# V0p2_Main_PCB2.net
KiCad netlist of a schematic drawn in EAGLE
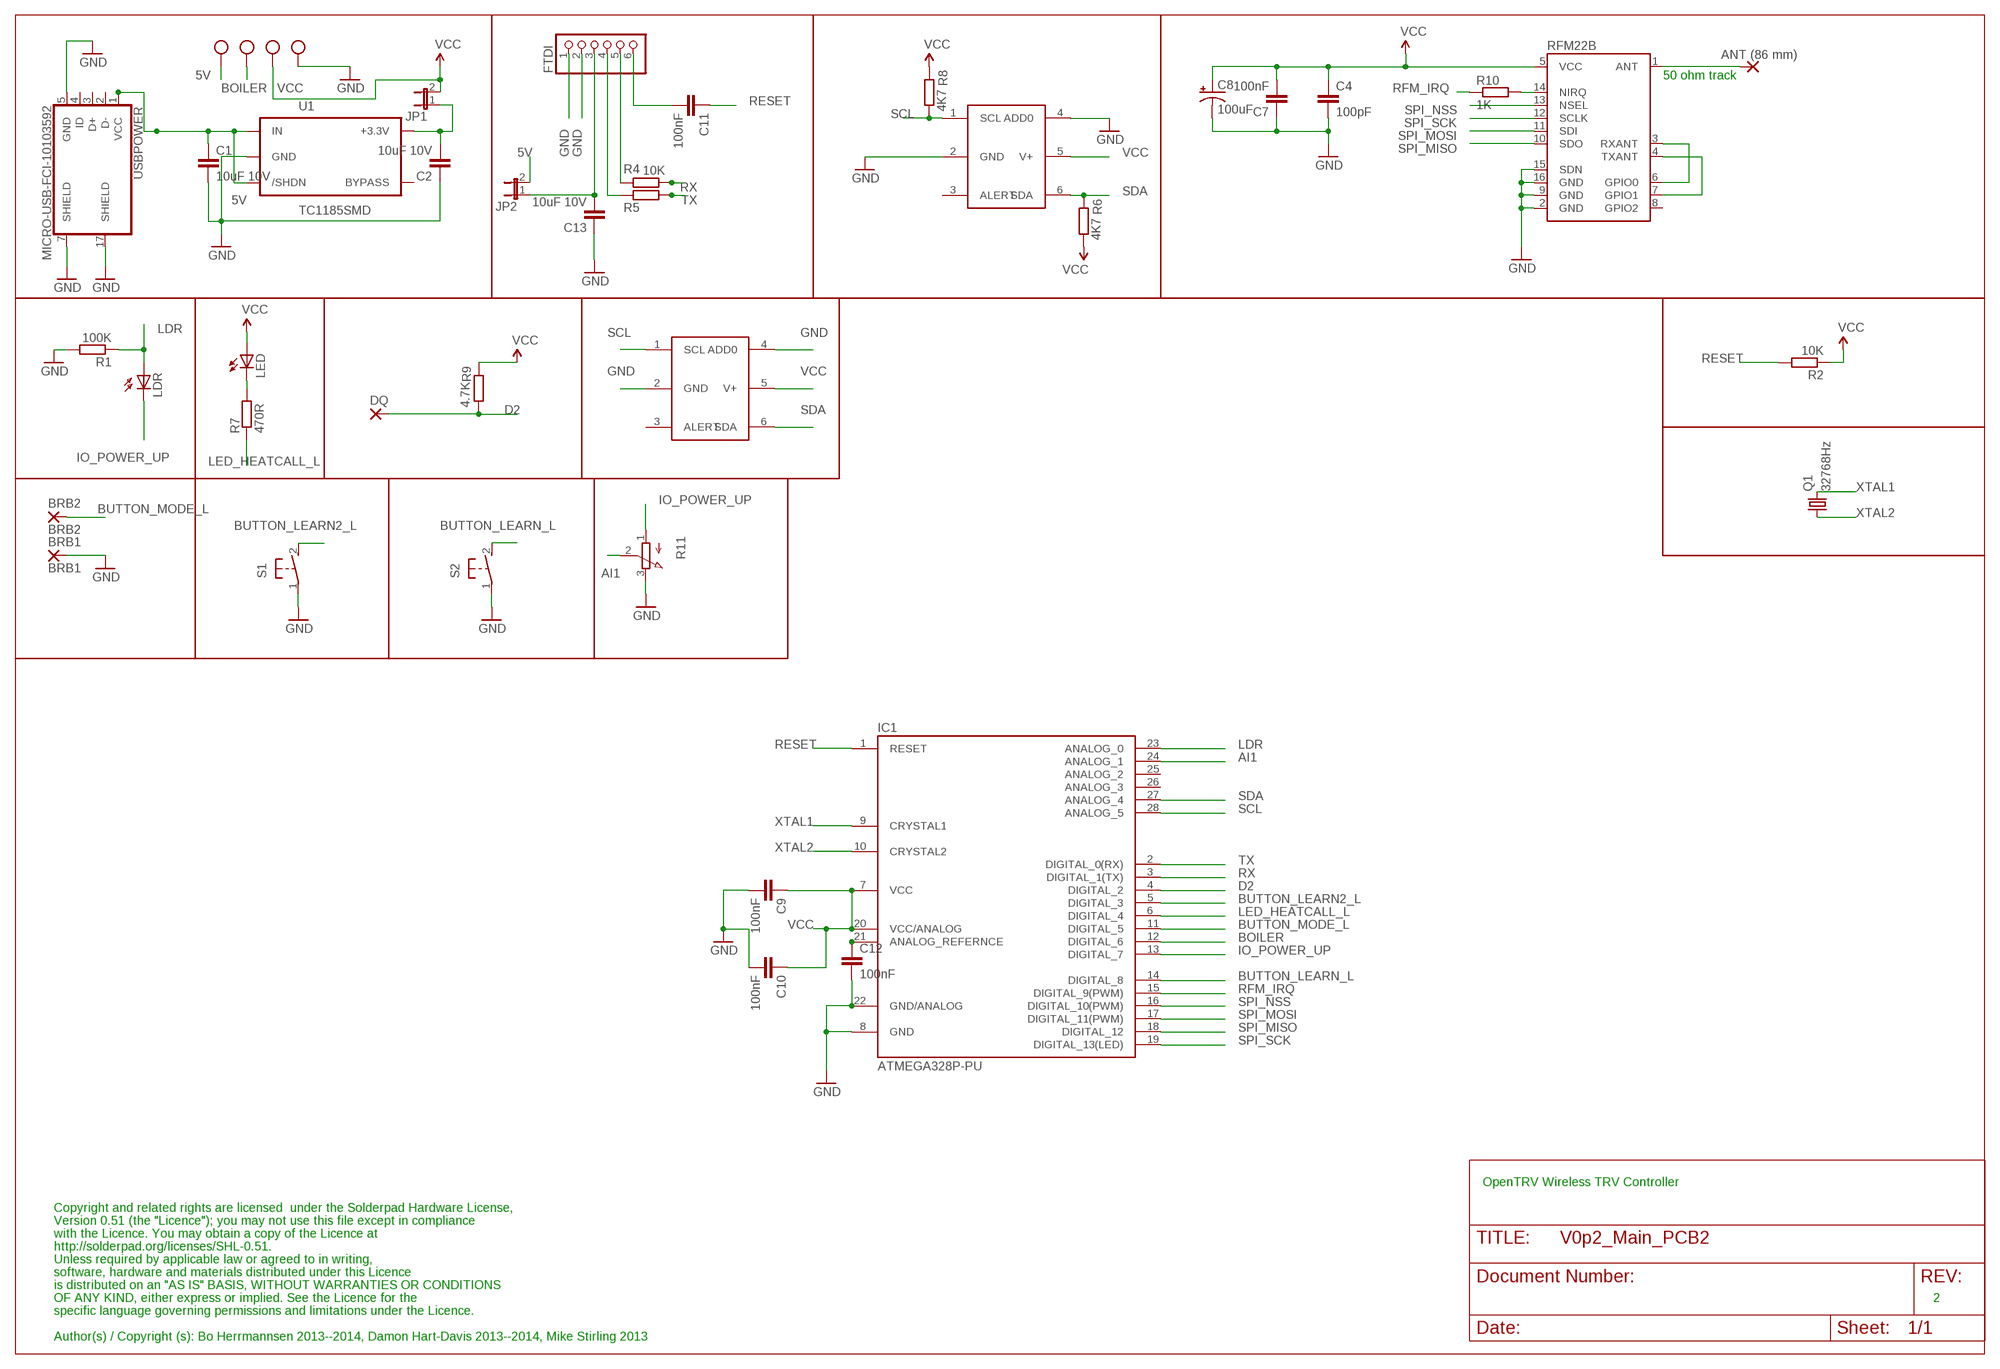
[diagram p0: schematic, sheet 1]

(export (version "E")
  (design (tool "Eeschema 10.0.6"))
  (components
    (comp (ref "ANT")
      (value "ANT (86 mm)")
      (footprint "eagle-import:2,15_1,0")
      (libsource (lib "eagle-import") (part "2,15/1,0"))
    )
    (comp (ref "BRB1")
      (value "BRB1")
      (footprint "eagle-import:2,15_1,0")
      (libsource (lib "eagle-import") (part "2,15/1,0"))
    )
    (comp (ref "BRB2")
      (value "BRB2")
      (footprint "eagle-import:2,15_1,0")
      (libsource (lib "eagle-import") (part "2,15/1,0"))
    )
    (comp (ref "C1")
      (value "10uF 10V")
      (footprint "eagle-import:0603-CAP")
      (libsource (lib "eagle-import") (part "CAP0603-CAP"))
    )
    (comp (ref "C2")
      (value "10uF 10V")
      (footprint "eagle-import:0603-CAP")
      (libsource (lib "eagle-import") (part "CAP0603-CAP"))
    )
    (comp (ref "C4")
      (value "100pF")
      (footprint "eagle-import:0603-CAP")
      (libsource (lib "eagle-import") (part "CAP0603-CAP"))
    )
    (comp (ref "C7")
      (value "100nF")
      (footprint "eagle-import:0603-CAP")
      (libsource (lib "eagle-import") (part "CAP0603-CAP"))
    )
    (comp (ref "C8")
      (value "100uF")
      (footprint "eagle-import:EIA3216")
      (libsource (lib "eagle-import") (part "CAP_POL1206"))
    )
    (comp (ref "C9")
      (value "100nF")
      (footprint "eagle-import:0603-CAP")
      (libsource (lib "eagle-import") (part "CAP0603-CAP"))
    )
    (comp (ref "C10")
      (value "100nF")
      (footprint "eagle-import:0603-CAP")
      (libsource (lib "eagle-import") (part "CAP0603-CAP"))
    )
    (comp (ref "C11")
      (value "100nF")
      (footprint "eagle-import:0603-CAP")
      (libsource (lib "eagle-import") (part "CAP0603-CAP"))
    )
    (comp (ref "C12")
      (value "100nF")
      (footprint "eagle-import:0603-CAP")
      (libsource (lib "eagle-import") (part "CAP0603-CAP"))
    )
    (comp (ref "C13")
      (value "10uF 10V")
      (footprint "eagle-import:0603-CAP")
      (libsource (lib "eagle-import") (part "CAP0603-CAP"))
    )
    (comp (ref "DQ")
      (value "2,15/1,0")
      (footprint "eagle-import:2,15_1,0")
      (libsource (lib "eagle-import") (part "2,15/1,0"))
    )
    (comp (ref "FTDI")
      (value "PINHD-1X6/90")
      (footprint "eagle-import:1X06_90")
      (libsource (lib "eagle-import") (part "PINHD-1X6/90"))
    )
    (comp (ref "IC1")
      (value "ATMEGA328P-PU")
      (footprint "eagle-import:DIL28-3")
      (libsource (lib "eagle-import") (part "ATMEGA8-PU"))
    )
    (comp (ref "JP1")
      (value "JP1E")
      (footprint "eagle-import:JP1")
      (libsource (lib "eagle-import") (part "JP1E"))
    )
    (comp (ref "JP2")
      (value "JP1E")
      (footprint "eagle-import:JP1")
      (libsource (lib "eagle-import") (part "JP1E"))
    )
    (comp (ref "LDR")
      (value "BPX65")
      (footprint "eagle-import:BPX65")
      (fields (field (name "MPN") "BPX65."))
      (libsource (lib "eagle-import") (part "BPX65"))
    )
    (comp (ref "LED")
      (value "LED3MM")
      (footprint "eagle-import:LED3MM")
      (libsource (lib "eagle-import") (part "LED3MM"))
    )
    (comp (ref "Q1")
      (value "32768Hz")
      (footprint "eagle-import:MC-306")
      (fields (field (name "MPN") "MC-306 60.0KHZ  100PPM ,12.5PF"))
      (libsource (lib "eagle-import") (part "MC-306"))
    )
    (comp (ref "R1")
      (value "100K")
      (footprint "eagle-import:R0603")
      (libsource (lib "eagle-import") (part "R-EU_R0603"))
    )
    (comp (ref "R2")
      (value "10K")
      (footprint "eagle-import:R0603")
      (libsource (lib "eagle-import") (part "R-EU_R0603"))
    )
    (comp (ref "R4")
      (value "10K")
      (footprint "eagle-import:R0603")
      (libsource (lib "eagle-import") (part "R-EU_R0603"))
    )
    (comp (ref "R5")
      (value "10K")
      (footprint "eagle-import:R0603")
      (libsource (lib "eagle-import") (part "R-EU_R0603"))
    )
    (comp (ref "R6")
      (value "4K7")
      (footprint "eagle-import:R0603")
      (libsource (lib "eagle-import") (part "R-EU_R0603"))
    )
    (comp (ref "R7")
      (value "470R")
      (footprint "eagle-import:R0603")
      (libsource (lib "eagle-import") (part "R-EU_R0603"))
    )
    (comp (ref "R8")
      (value "4K7")
      (footprint "eagle-import:R0603")
      (libsource (lib "eagle-import") (part "R-EU_R0603"))
    )
    (comp (ref "R9")
      (value "4.7K")
      (footprint "eagle-import:R0603")
      (libsource (lib "eagle-import") (part "R-EU_R0603"))
    )
    (comp (ref "R10")
      (value "1K")
      (footprint "eagle-import:R0603")
      (libsource (lib "eagle-import") (part "R-EU_R0603"))
    )
    (comp (ref "R11")
      (value "EVUE2A")
      (footprint "eagle-import:EVUE")
      (libsource (lib "eagle-import") (part "EVUE2A"))
    )
    (comp (ref "RFM22B")
      (value "RFM22SMD")
      (footprint "eagle-import:RFM22-XXX-S2")
      (libsource (lib "eagle-import") (part "RFM22SMD"))
    )
    (comp (ref "S1")
      (value "31-XX")
      (footprint "eagle-import:B3F-31XX")
      (libsource (lib "eagle-import") (part "31-XX"))
    )
    (comp (ref "S2")
      (value "31-XX")
      (footprint "eagle-import:B3F-31XX")
      (libsource (lib "eagle-import") (part "31-XX"))
    )
    (comp (ref "TMP1")
      (value "TMP1")
      (footprint "eagle-import:TMP112")
      (libsource (lib "eagle-import") (part "TMP112"))
    )
    (comp (ref "TMP2")
      (value "TMP2")
      (footprint "eagle-import:TMP112")
      (libsource (lib "eagle-import") (part "TMP112_2_TMP112"))
    )
    (comp (ref "U1")
      (value "TC1185SMD")
      (footprint "eagle-import:TC1185")
      (libsource (lib "eagle-import") (part "TC1185SMD"))
    )
    (comp (ref "USBPOWER")
      (value "MICRO-USB-FCI-10103592")
      (footprint "eagle-import:MICRO-USB-FCI-10103592")
      (libsource (lib "eagle-import") (part "MICRO-USB-FCI-10103592"))
    )
    (comp (ref "X1")
      (value "W237-102")
      (footprint "eagle-import:SCREWTERMINAL")
      (fields (field (name "MPN") "237-102"))
      (libsource (lib "eagle-import") (part "W237-102"))
    )
    (comp (ref "X2")
      (value "W237-102")
      (footprint "eagle-import:SCREWTERMINAL")
      (fields (field (name "MPN") "237-102"))
      (libsource (lib "eagle-import") (part "W237-102"))
    )
  )
  (nets
    (net (code "1") (name "/5V") (class "Default")
      (node (ref "C1") (pin "1") (pinfunction "1_1") (pintype "passive"))
      (node (ref "JP2") (pin "2") (pinfunction "2_2") (pintype "passive"))
      (node (ref "U1") (pin "1") (pinfunction "IN_1") (pintype "passive"))
      (node (ref "U1") (pin "3") (pinfunction "/SHDN_3") (pintype "passive"))
      (node (ref "USBPOWER") (pin "1") (pinfunction "VCC_1") (pintype "bidirectional"))
      (node (ref "X1") (pin "2") (pinfunction "KL_2") (pintype "passive"))
    )
    (net (code "2") (name "/AI1") (class "Default")
      (node (ref "IC1") (pin "24") (pinfunction "ANALOG_1_24") (pintype "bidirectional"))
      (node (ref "R11") (pin "2") (pinfunction "S_2") (pintype "passive"))
    )
    (net (code "3") (name "/BOILER") (class "Default")
      (node (ref "IC1") (pin "12") (pinfunction "DIGITAL_6_12") (pintype "bidirectional"))
      (node (ref "X1") (pin "1") (pinfunction "KL_1") (pintype "passive"))
    )
    (net (code "4") (name "/BUTTON_LEARN2_L") (class "Default")
      (node (ref "IC1") (pin "5") (pinfunction "DIGITAL_3_5") (pintype "bidirectional"))
      (node (ref "S1") (pin "2") (pinfunction "S_2") (pintype "passive"))
    )
    (net (code "5") (name "/BUTTON_LEARN_L") (class "Default")
      (node (ref "IC1") (pin "14") (pinfunction "DIGITAL_8_14") (pintype "bidirectional"))
      (node (ref "S2") (pin "2") (pinfunction "S_2") (pintype "passive"))
    )
    (net (code "6") (name "/BUTTON_MODE_L") (class "Default")
      (node (ref "BRB2") (pin "1") (pinfunction "P_1") (pintype "passive"))
      (node (ref "IC1") (pin "11") (pinfunction "DIGITAL_5_11") (pintype "bidirectional"))
    )
    (net (code "7") (name "/D2") (class "Default")
      (node (ref "DQ") (pin "1") (pinfunction "P_1") (pintype "passive"))
      (node (ref "IC1") (pin "4") (pinfunction "DIGITAL_2_4") (pintype "bidirectional"))
      (node (ref "R9") (pin "1") (pinfunction "1_1") (pintype "passive"))
    )
    (net (code "8") (name "/IO_POWER_UP") (class "Default")
      (node (ref "IC1") (pin "13") (pinfunction "DIGITAL_7_13") (pintype "bidirectional"))
      (node (ref "LDR") (pin "K") (pinfunction "C_K") (pintype "passive"))
      (node (ref "R11") (pin "1") (pinfunction "A_1") (pintype "passive"))
    )
    (net (code "9") (name "/LDR") (class "Default")
      (node (ref "IC1") (pin "23") (pinfunction "ANALOG_0_23") (pintype "bidirectional"))
      (node (ref "LDR") (pin "A") (pinfunction "A_A") (pintype "passive"))
      (node (ref "R1") (pin "1") (pinfunction "1_1") (pintype "passive"))
    )
    (net (code "10") (name "/LED_HEATCALL_L") (class "Default")
      (node (ref "IC1") (pin "6") (pinfunction "DIGITAL_4_6") (pintype "bidirectional"))
      (node (ref "R7") (pin "1") (pinfunction "1_1") (pintype "passive"))
    )
    (net (code "11") (name "/RESET") (class "Default")
      (node (ref "C11") (pin "1") (pinfunction "1_1") (pintype "passive"))
      (node (ref "IC1") (pin "1") (pinfunction "RESET_1") (pintype "bidirectional"))
      (node (ref "R2") (pin "2") (pinfunction "2_2") (pintype "passive"))
    )
    (net (code "12") (name "/RFM_IRQ") (class "Default")
      (node (ref "IC1") (pin "15") (pinfunction "DIGITAL_9(PWM)_15") (pintype "bidirectional"))
      (node (ref "R10") (pin "1") (pinfunction "1_1") (pintype "passive"))
    )
    (net (code "13") (name "/RX") (class "Default")
      (node (ref "IC1") (pin "3") (pinfunction "DIGITAL_1(TX)_3") (pintype "bidirectional"))
      (node (ref "R4") (pin "1") (pinfunction "1_1") (pintype "passive"))
    )
    (net (code "14") (name "/SCL") (class "Default")
      (node (ref "IC1") (pin "28") (pinfunction "ANALOG_5_28") (pintype "bidirectional"))
      (node (ref "R8") (pin "1") (pinfunction "1_1") (pintype "passive"))
      (node (ref "TMP1") (pin "1") (pinfunction "SCL_1") (pintype "bidirectional"))
      (node (ref "TMP2") (pin "1") (pinfunction "SCL_1") (pintype "bidirectional"))
    )
    (net (code "15") (name "/SDA") (class "Default")
      (node (ref "IC1") (pin "27") (pinfunction "ANALOG_4_27") (pintype "bidirectional"))
      (node (ref "R6") (pin "2") (pinfunction "2_2") (pintype "passive"))
      (node (ref "TMP1") (pin "6") (pinfunction "SDA_6") (pintype "bidirectional"))
      (node (ref "TMP2") (pin "6") (pinfunction "SDA_6") (pintype "bidirectional"))
    )
    (net (code "16") (name "/SPI_MISO") (class "Default")
      (node (ref "IC1") (pin "18") (pinfunction "DIGITAL_12_18") (pintype "bidirectional"))
      (node (ref "RFM22B") (pin "10") (pinfunction "SDO_10") (pintype "output"))
    )
    (net (code "17") (name "/SPI_MOSI") (class "Default")
      (node (ref "IC1") (pin "17") (pinfunction "DIGITAL_11(PWM)_17") (pintype "bidirectional"))
      (node (ref "RFM22B") (pin "11") (pinfunction "SDI_11") (pintype "input"))
    )
    (net (code "18") (name "/SPI_NSS") (class "Default")
      (node (ref "IC1") (pin "16") (pinfunction "DIGITAL_10(PWM)_16") (pintype "bidirectional"))
      (node (ref "RFM22B") (pin "13") (pinfunction "NSEL_13") (pintype "input"))
    )
    (net (code "19") (name "/SPI_SCK") (class "Default")
      (node (ref "IC1") (pin "19") (pinfunction "DIGITAL_13(LED)_19") (pintype "bidirectional"))
      (node (ref "RFM22B") (pin "12") (pinfunction "SCLK_12") (pintype "input"))
    )
    (net (code "20") (name "/TX") (class "Default")
      (node (ref "IC1") (pin "2") (pinfunction "DIGITAL_0(RX)_2") (pintype "bidirectional"))
      (node (ref "R5") (pin "1") (pinfunction "1_1") (pintype "passive"))
    )
    (net (code "21") (name "/XTAL1") (class "Default")
      (node (ref "IC1") (pin "9") (pinfunction "CRYSTAL1_9") (pintype "bidirectional"))
      (node (ref "Q1") (pin "4") (pinfunction "2_4") (pintype "passive"))
    )
    (net (code "22") (name "/XTAL2") (class "Default")
      (node (ref "IC1") (pin "10") (pinfunction "CRYSTAL2_10") (pintype "bidirectional"))
      (node (ref "Q1") (pin "1") (pinfunction "1_1") (pintype "passive"))
    )
    (net (code "23") (name "GND") (class "Default")
      (node (ref "BRB1") (pin "1") (pinfunction "P_1") (pintype "passive"))
      (node (ref "C1") (pin "2") (pinfunction "2_2") (pintype "passive"))
      (node (ref "C10") (pin "2") (pinfunction "2_2") (pintype "passive"))
      (node (ref "C12") (pin "2") (pinfunction "2_2") (pintype "passive"))
      (node (ref "C13") (pin "1") (pinfunction "1_1") (pintype "passive"))
      (node (ref "C2") (pin "1") (pinfunction "1_1") (pintype "passive"))
      (node (ref "C4") (pin "2") (pinfunction "2_2") (pintype "passive"))
      (node (ref "C7") (pin "1") (pinfunction "1_1") (pintype "passive"))
      (node (ref "C8") (pin "C") (pinfunction "-_C") (pintype "passive"))
      (node (ref "C9") (pin "2") (pinfunction "2_2") (pintype "passive"))
      (node (ref "FTDI") (pin "1") (pinfunction "1_1") (pintype "passive"))
      (node (ref "FTDI") (pin "2") (pinfunction "2_2") (pintype "passive"))
      (node (ref "IC1") (pin "22") (pinfunction "GND/ANALOG_22") (pintype "power_in"))
      (node (ref "IC1") (pin "8") (pinfunction "GND_8") (pintype "power_in"))
      (node (ref "R1") (pin "2") (pinfunction "2_2") (pintype "passive"))
      (node (ref "R11") (pin "3") (pinfunction "E_3") (pintype "passive"))
      (node (ref "RFM22B") (pin "15") (pinfunction "SDN_15") (pintype "input"))
      (node (ref "RFM22B") (pin "16") (pinfunction "GND_16") (pintype "power_in"))
      (node (ref "RFM22B") (pin "2") (pinfunction "GND_2") (pintype "power_in"))
      (node (ref "RFM22B") (pin "9") (pinfunction "GND_9") (pintype "power_in"))
      (node (ref "S1") (pin "1") (pinfunction "P_1") (pintype "passive"))
      (node (ref "S2") (pin "1") (pinfunction "P_1") (pintype "passive"))
      (node (ref "TMP1") (pin "2") (pinfunction "GND_2") (pintype "bidirectional"))
      (node (ref "TMP1") (pin "4") (pinfunction "ADD0_4") (pintype "bidirectional"))
      (node (ref "TMP2") (pin "2") (pinfunction "GND_2") (pintype "bidirectional"))
      (node (ref "TMP2") (pin "4") (pinfunction "ADD0_4") (pintype "bidirectional"))
      (node (ref "U1") (pin "2") (pinfunction "GND_2") (pintype "passive"))
      (node (ref "USBPOWER") (pin "17") (pinfunction "SHIELD_17") (pintype "bidirectional"))
      (node (ref "USBPOWER") (pin "5") (pinfunction "GND_5") (pintype "bidirectional"))
      (node (ref "USBPOWER") (pin "7") (pinfunction "SHIELD_7") (pintype "bidirectional"))
      (node (ref "X2") (pin "2") (pinfunction "KL_2") (pintype "passive"))
    )
    (net (code "24") (name "Net-(ANT-P)") (class "Default")
      (node (ref "ANT") (pin "1") (pinfunction "P_1") (pintype "passive"))
      (node (ref "RFM22B") (pin "1") (pinfunction "ANT_1") (pintype "bidirectional"))
    )
    (net (code "25") (name "Net-(C11-Pad2)") (class "Default")
      (node (ref "C11") (pin "2") (pinfunction "2_2") (pintype "passive"))
      (node (ref "FTDI") (pin "6") (pinfunction "6_6") (pintype "passive"))
    )
    (net (code "26") (name "Net-(C13-Pad2)") (class "Default")
      (node (ref "C13") (pin "2") (pinfunction "2_2") (pintype "passive"))
      (node (ref "FTDI") (pin "3") (pinfunction "3_3") (pintype "passive"))
      (node (ref "JP2") (pin "1") (pinfunction "1_1") (pintype "passive"))
    )
    (net (code "27") (name "Net-(FTDI-Pad4)") (class "Default")
      (node (ref "FTDI") (pin "4") (pinfunction "4_4") (pintype "passive"))
      (node (ref "R5") (pin "2") (pinfunction "2_2") (pintype "passive"))
    )
    (net (code "28") (name "Net-(FTDI-Pad5)") (class "Default")
      (node (ref "FTDI") (pin "5") (pinfunction "5_5") (pintype "passive"))
      (node (ref "R4") (pin "2") (pinfunction "2_2") (pintype "passive"))
    )
    (net (code "29") (name "Net-(IC1-ANALOG_REFERNCE)") (class "Default")
      (node (ref "C12") (pin "1") (pinfunction "1_1") (pintype "passive"))
      (node (ref "IC1") (pin "21") (pinfunction "ANALOG_REFERNCE_21") (pintype "passive"))
    )
    (net (code "30") (name "Net-(LED-C)") (class "Default")
      (node (ref "LED") (pin "K") (pinfunction "C_K") (pintype "passive"))
      (node (ref "R7") (pin "2") (pinfunction "2_2") (pintype "passive"))
    )
    (net (code "31") (name "Net-(RFM22B-GPIO0)") (class "Default")
      (node (ref "RFM22B") (pin "3") (pinfunction "RXANT_3") (pintype "input"))
      (node (ref "RFM22B") (pin "6") (pinfunction "GPIO0_6") (pintype "bidirectional"))
    )
    (net (code "32") (name "Net-(RFM22B-GPIO1)") (class "Default")
      (node (ref "RFM22B") (pin "4") (pinfunction "TXANT_4") (pintype "input"))
      (node (ref "RFM22B") (pin "7") (pinfunction "GPIO1_7") (pintype "bidirectional"))
    )
    (net (code "33") (name "Net-(RFM22B-NIRQ)") (class "Default")
      (node (ref "R10") (pin "2") (pinfunction "2_2") (pintype "passive"))
      (node (ref "RFM22B") (pin "14") (pinfunction "NIRQ_14") (pintype "output"))
    )
    (net (code "34") (name "Net-(U1-+3.3V)") (class "Default")
      (node (ref "C2") (pin "2") (pinfunction "2_2") (pintype "passive"))
      (node (ref "JP1") (pin "1") (pinfunction "1_1") (pintype "passive"))
      (node (ref "U1") (pin "5") (pinfunction "+3.3V_5") (pintype "power_in"))
    )
    (net (code "35") (name "VCC") (class "Default")
      (node (ref "C10") (pin "1") (pinfunction "1_1") (pintype "passive"))
      (node (ref "C4") (pin "1") (pinfunction "1_1") (pintype "passive"))
      (node (ref "C7") (pin "2") (pinfunction "2_2") (pintype "passive"))
      (node (ref "C8") (pin "A") (pinfunction "+_A") (pintype "passive"))
      (node (ref "C9") (pin "1") (pinfunction "1_1") (pintype "passive"))
      (node (ref "IC1") (pin "20") (pinfunction "VCC/ANALOG_20") (pintype "passive"))
      (node (ref "IC1") (pin "7") (pinfunction "VCC_7") (pintype "power_in"))
      (node (ref "JP1") (pin "2") (pinfunction "2_2") (pintype "passive"))
      (node (ref "LED") (pin "A") (pinfunction "A_A") (pintype "passive"))
      (node (ref "R2") (pin "1") (pinfunction "1_1") (pintype "passive"))
      (node (ref "R6") (pin "1") (pinfunction "1_1") (pintype "passive"))
      (node (ref "R8") (pin "2") (pinfunction "2_2") (pintype "passive"))
      (node (ref "R9") (pin "2") (pinfunction "2_2") (pintype "passive"))
      (node (ref "RFM22B") (pin "5") (pinfunction "VCC_5") (pintype "bidirectional"))
      (node (ref "TMP1") (pin "5") (pinfunction "V+_5") (pintype "bidirectional"))
      (node (ref "TMP2") (pin "5") (pinfunction "V+_5") (pintype "bidirectional"))
      (node (ref "X2") (pin "1") (pinfunction "KL_1") (pintype "passive"))
    )
    (net (code "36") (name "unconnected-(IC1-ANALOG_2-Pad25)") (class "Default")
      (node (ref "IC1") (pin "25") (pinfunction "ANALOG_2_25") (pintype "bidirectional"))
    )
    (net (code "37") (name "unconnected-(IC1-ANALOG_3-Pad26)") (class "Default")
      (node (ref "IC1") (pin "26") (pinfunction "ANALOG_3_26") (pintype "bidirectional"))
    )
    (net (code "38") (name "unconnected-(RFM22B-GPIO2-Pad8)") (class "Default")
      (node (ref "RFM22B") (pin "8") (pinfunction "GPIO2_8") (pintype "bidirectional"))
    )
    (net (code "39") (name "unconnected-(TMP1-ALERT-Pad3)") (class "Default")
      (node (ref "TMP1") (pin "3") (pinfunction "ALERT_3") (pintype "bidirectional"))
    )
    (net (code "40") (name "unconnected-(TMP2-ALERT-Pad3)") (class "Default")
      (node (ref "TMP2") (pin "3") (pinfunction "ALERT_3") (pintype "bidirectional"))
    )
    (net (code "41") (name "unconnected-(U1-BYPASS-Pad4)") (class "Default")
      (node (ref "U1") (pin "4") (pinfunction "BYPASS_4") (pintype "passive"))
    )
    (net (code "42") (name "unconnected-(USBPOWER-D+-Pad3)") (class "Default")
      (node (ref "USBPOWER") (pin "3") (pinfunction "D+_3") (pintype "bidirectional"))
    )
    (net (code "43") (name "unconnected-(USBPOWER-D--Pad2)") (class "Default")
      (node (ref "USBPOWER") (pin "2") (pinfunction "D-_2") (pintype "bidirectional"))
    )
    (net (code "44") (name "unconnected-(USBPOWER-ID-Pad4)") (class "Default")
      (node (ref "USBPOWER") (pin "4") (pinfunction "ID_4") (pintype "bidirectional"))
    )
  )
)
